# SoM_-_PullUp_PullDown.net
KiCad netlist of a schematic drawn in Altium Designer
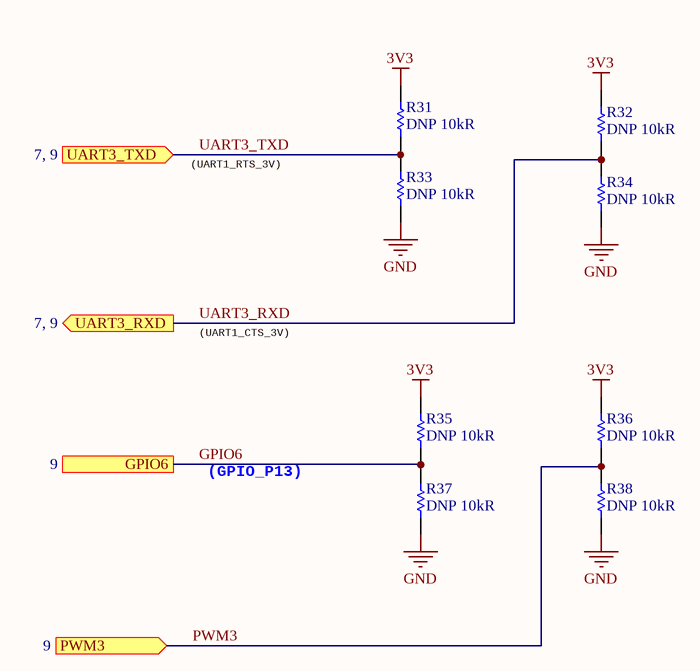
[diagram p0: SoM - PullUp PullDown.SchDoc]

(export (version "E")
  (design (tool "Eeschema 10.0.6"))
  (components
    (comp (ref "R31")
      (value "DNP 10kR")
      (footprint "RESC2013X60X35NL10T20")
      (fields (field (name "MANUFACTURER") "Yageo"))
      (libsource (lib "Altium Content Vault") (part "RES-2"))
    )
    (comp (ref "R32")
      (value "DNP 10kR")
      (footprint "RESC2013X60X35NL10T20")
      (fields (field (name "MANUFACTURER") "Yageo"))
      (libsource (lib "Altium Content Vault") (part "RES-2"))
    )
    (comp (ref "R33")
      (value "DNP 10kR")
      (footprint "RESC2013X60X35NL10T20")
      (fields (field (name "MANUFACTURER") "Yageo"))
      (libsource (lib "Altium Content Vault") (part "RES-2"))
    )
    (comp (ref "R34")
      (value "DNP 10kR")
      (footprint "RESC2013X60X35NL10T20")
      (fields (field (name "MANUFACTURER") "Yageo"))
      (libsource (lib "Altium Content Vault") (part "RES-2"))
    )
    (comp (ref "R35")
      (value "DNP 10kR")
      (footprint "RESC2013X60X35NL10T20")
      (fields (field (name "MANUFACTURER") "Yageo"))
      (libsource (lib "Altium Content Vault") (part "RES-2"))
    )
    (comp (ref "R36")
      (value "DNP 10kR")
      (footprint "RESC2013X60X35NL10T20")
      (fields (field (name "MANUFACTURER") "Yageo"))
      (libsource (lib "Altium Content Vault") (part "RES-2"))
    )
    (comp (ref "R37")
      (value "DNP 10kR")
      (footprint "RESC2013X60X35NL10T20")
      (fields (field (name "MANUFACTURER") "Yageo"))
      (libsource (lib "Altium Content Vault") (part "RES-2"))
    )
    (comp (ref "R38")
      (value "DNP 10kR")
      (footprint "RESC2013X60X35NL10T20")
      (fields (field (name "MANUFACTURER") "Yageo"))
      (libsource (lib "Altium Content Vault") (part "RES-2"))
    )
  )
  (nets
    (net (code "1") (name "/GPIO6") (class "Default")
      (node (ref "R35") (pin "2") (pinfunction "2_2") (pintype "passive"))
      (node (ref "R37") (pin "1") (pinfunction "1_1") (pintype "passive"))
    )
    (net (code "2") (name "/PWM3") (class "Default")
      (node (ref "R36") (pin "2") (pinfunction "2_2") (pintype "passive"))
      (node (ref "R38") (pin "1") (pinfunction "1_1") (pintype "passive"))
    )
    (net (code "3") (name "/UART3_RXD") (class "Default")
      (node (ref "R32") (pin "2") (pinfunction "2_2") (pintype "passive"))
      (node (ref "R34") (pin "1") (pinfunction "1_1") (pintype "passive"))
    )
    (net (code "4") (name "/UART3_TXD") (class "Default")
      (node (ref "R31") (pin "2") (pinfunction "2_2") (pintype "passive"))
      (node (ref "R33") (pin "1") (pinfunction "1_1") (pintype "passive"))
    )
    (net (code "5") (name "3V3") (class "Default")
      (node (ref "R31") (pin "1") (pinfunction "1_1") (pintype "passive"))
      (node (ref "R32") (pin "1") (pinfunction "1_1") (pintype "passive"))
      (node (ref "R35") (pin "1") (pinfunction "1_1") (pintype "passive"))
      (node (ref "R36") (pin "1") (pinfunction "1_1") (pintype "passive"))
    )
    (net (code "6") (name "GND") (class "Default")
      (node (ref "R33") (pin "2") (pinfunction "2_2") (pintype "passive"))
      (node (ref "R34") (pin "2") (pinfunction "2_2") (pintype "passive"))
      (node (ref "R37") (pin "2") (pinfunction "2_2") (pintype "passive"))
      (node (ref "R38") (pin "2") (pinfunction "2_2") (pintype "passive"))
    )
  )
)
